# E-12_USB_PD.net
KiCad netlist of a schematic drawn in Altium Designer
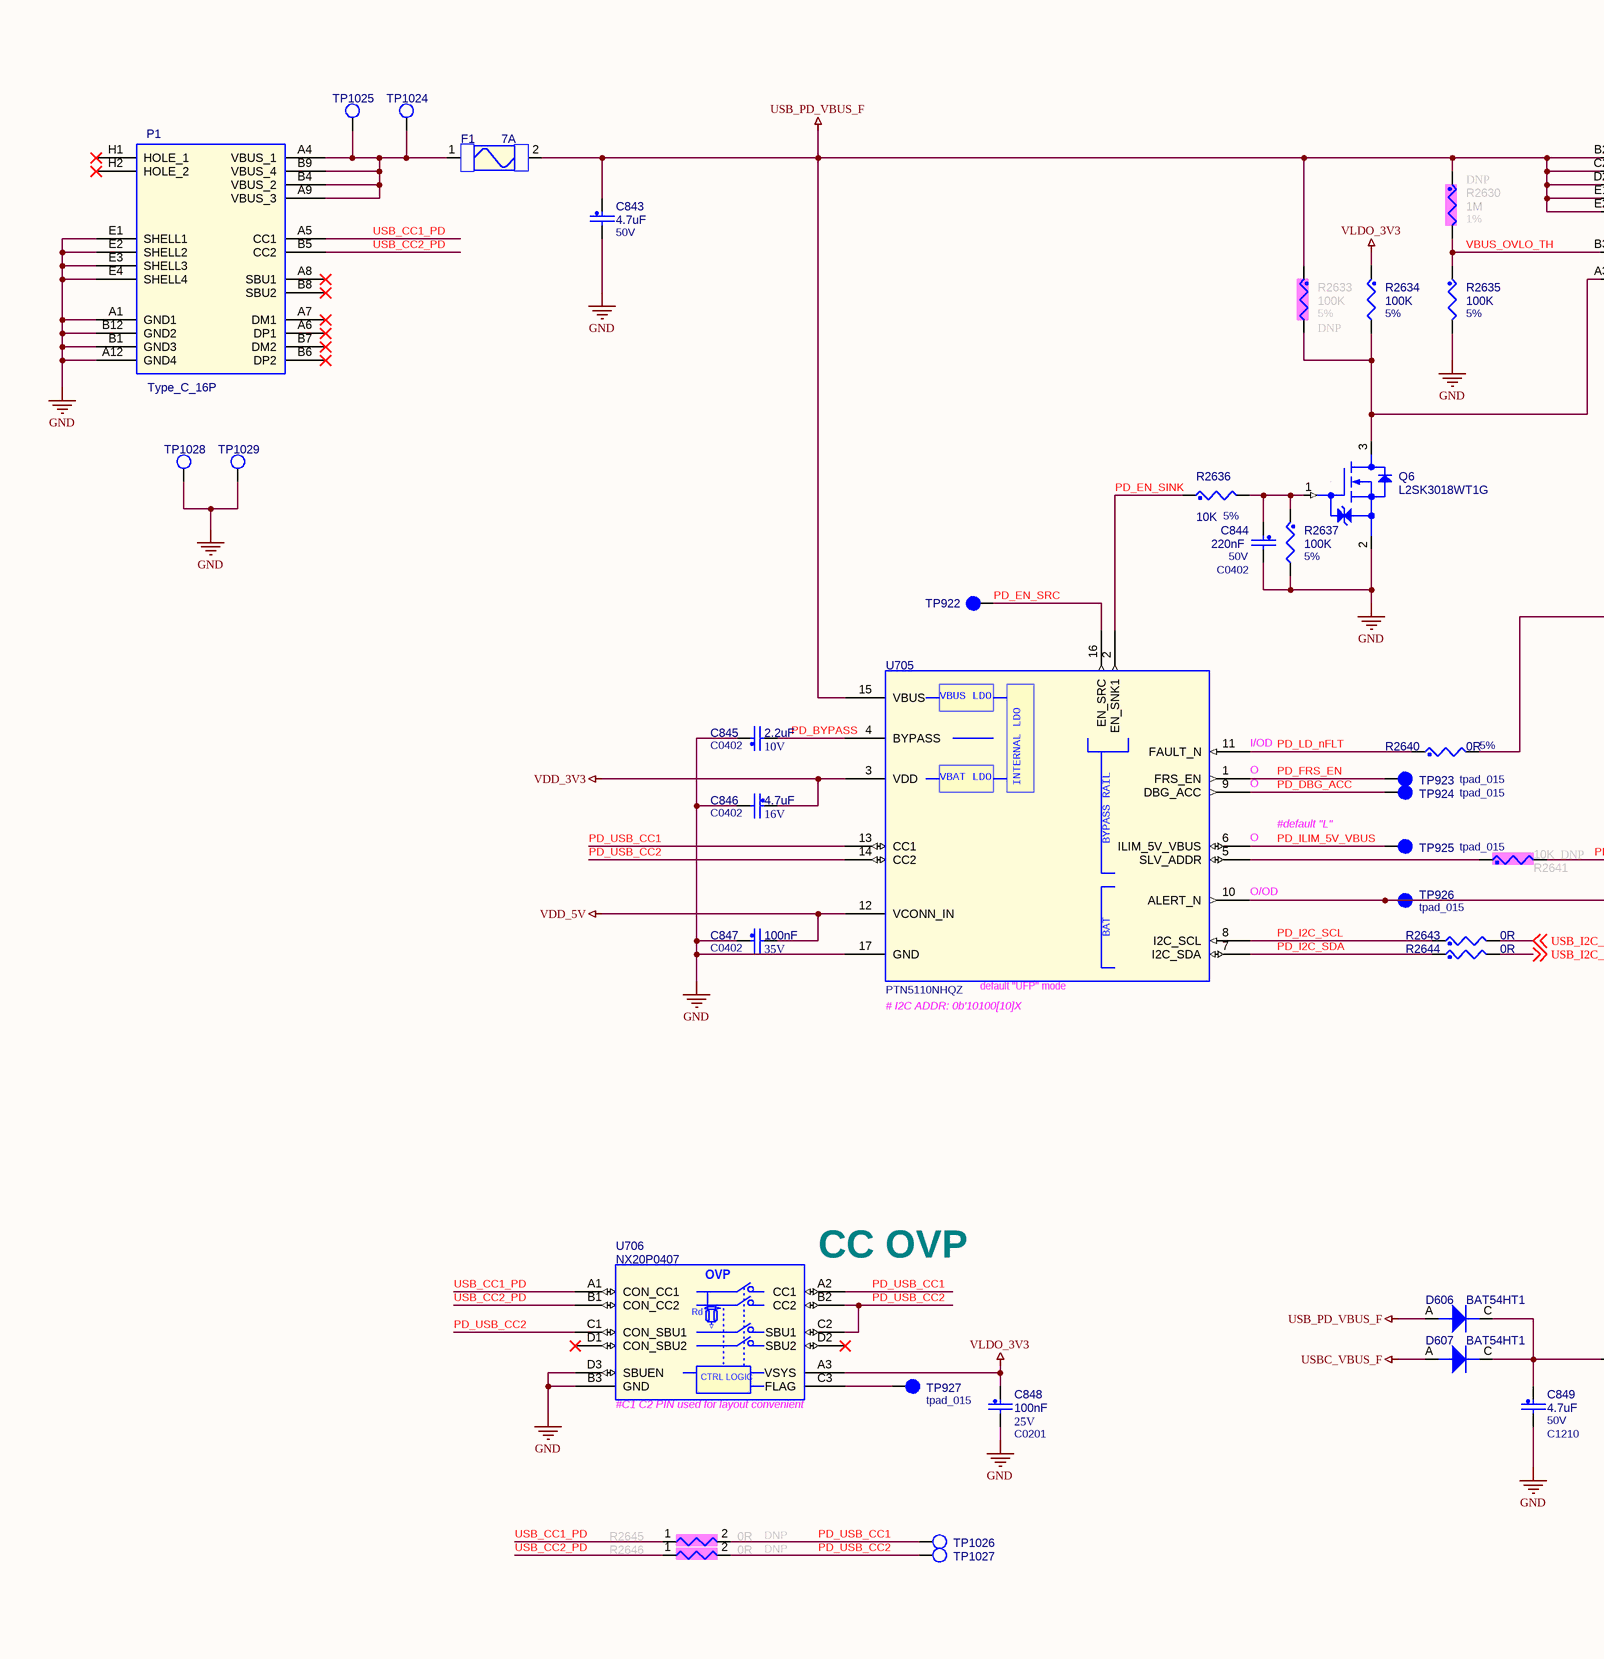
[diagram p0: E-12 USB PD.SchDoc, left]
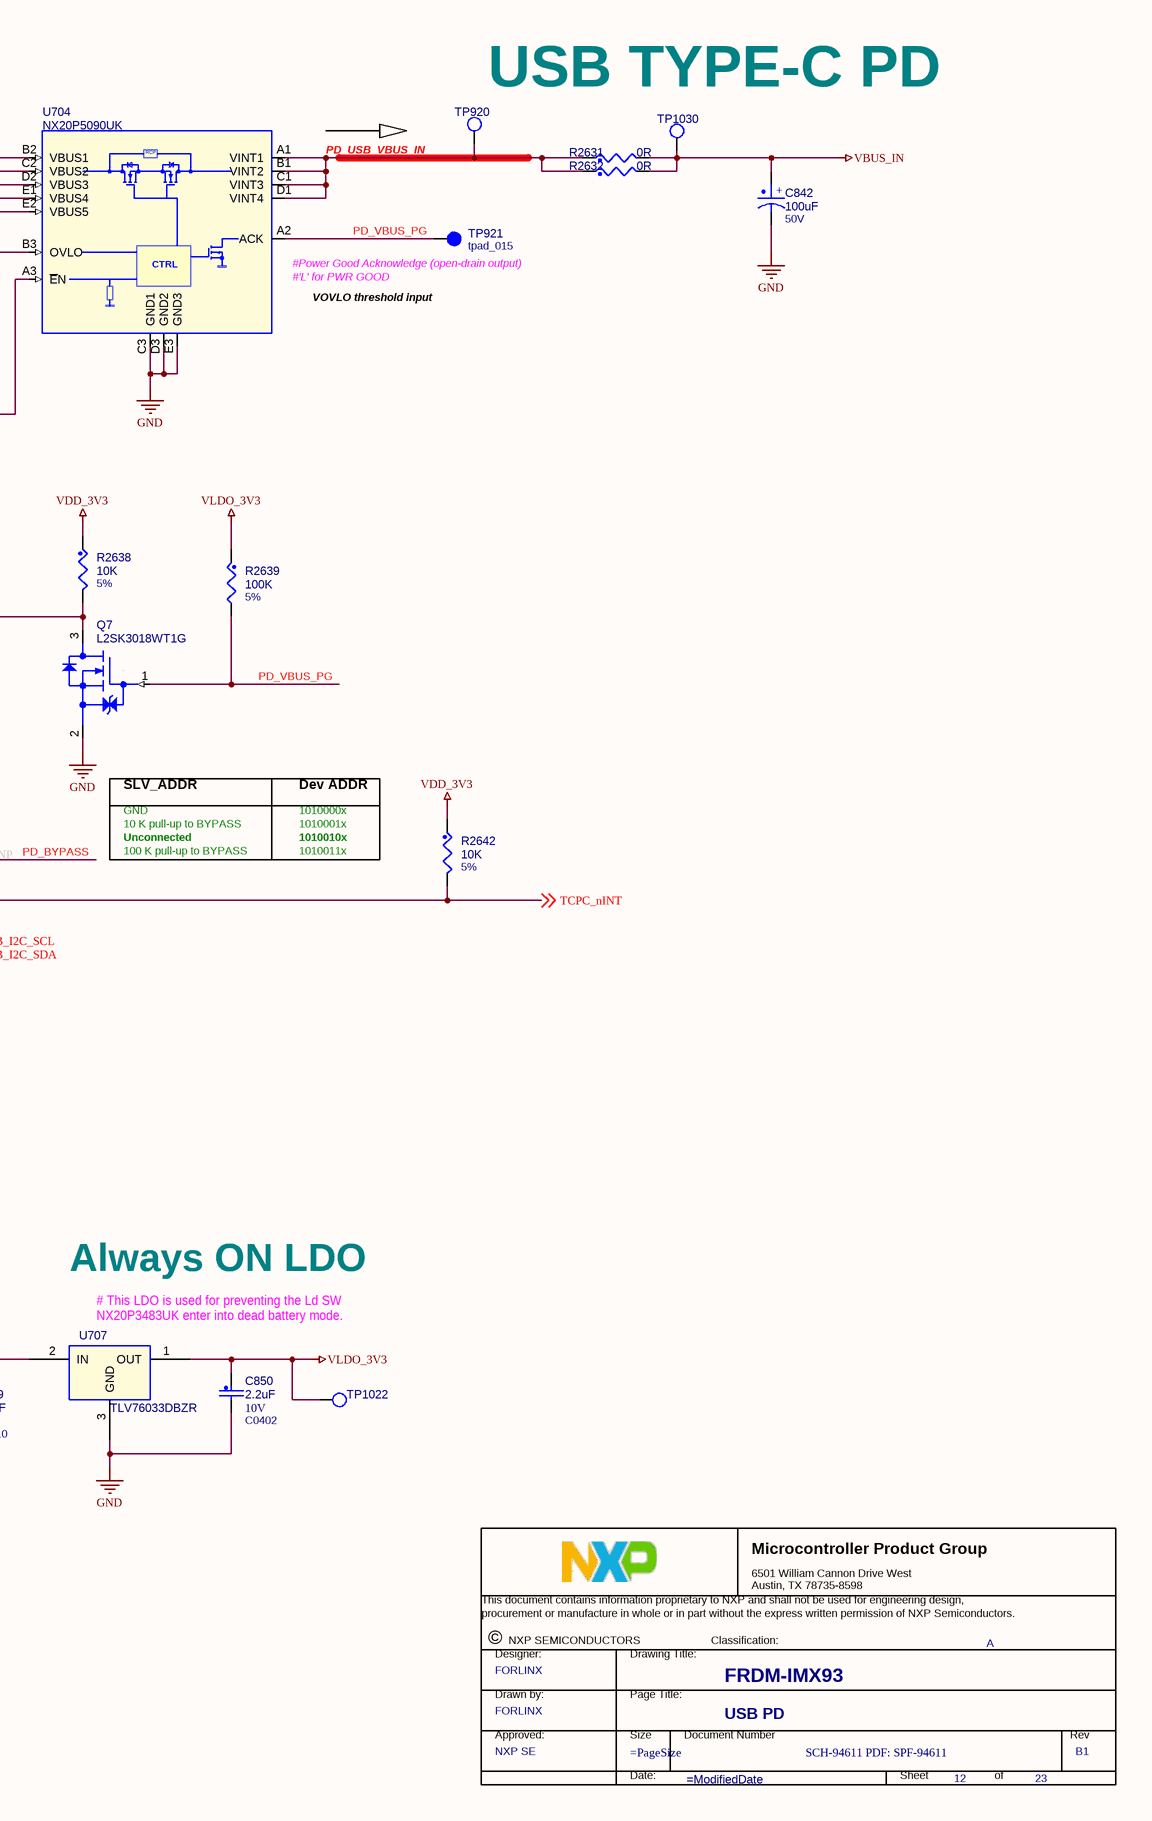
[diagram p1: E-12 USB PD.SchDoc, right]

(export (version "E")
  (design (tool "Eeschema 10.0.6"))
  (components
    (comp (ref "C842")
      (value "100uF")
      (footprint "cce6P3x7p7")
      (description "100uF,35V,6.3*7.7mm")
      (fields (field (name "VOLTAGE") "50V") (field (name "TOLERANCE") "20%"))
      (libsource (lib "*") (part "CAP_POL"))
    )
    (comp (ref "C843")
      (value "4.7uF")
      (footprint "C1210")
      (description "1210,4.7uF,50V,+/-10%,X7R")
      (fields (field (name "VOLTAGE") "50V") (field (name "TOLERANCE") "10%"))
      (libsource (lib "*") (part "CAP_NP"))
    )
    (comp (ref "C844")
      (value "220nF")
      (footprint "C0402")
      (description "0402,220nF,25V,+/-10%,X5R")
      (fields
        (field (name "VOLTAGE") "50V")
        (field (name "TOLERANCE") "10%")
        (field (name "PCB FOOTPRINT") "C0402")
      )
      (libsource (lib "*") (part "CAP_NP"))
    )
    (comp (ref "C845")
      (value "2.2uF")
      (footprint "C0402")
      (description "0402,2.2uF,10V,+/-10%,X5R")
      (fields
        (field (name "VOLTAGE") "10V")
        (field (name "TOLERANCE") "10%")
        (field (name "PCB FOOTPRINT") "C0402")
      )
      (libsource (lib "*") (part "CAP_NP"))
    )
    (comp (ref "C846")
      (value "4.7uF")
      (footprint "C0402")
      (description "0402,4.7uF,10V,+/-10%,X5R")
      (fields (field (name "VOLTAGE") "16V") (field (name "PCB FOOTPRINT") "C0402"))
      (libsource (lib "*") (part "CAP_NP"))
    )
    (comp (ref "C847")
      (value "100nF")
      (footprint "C0402")
      (description "0402,100nF,50V,+/-10%,X5R")
      (fields
        (field (name "VOLTAGE") "35V")
        (field (name "TOLERANCE") "10%")
        (field (name "PCB FOOTPRINT") "C0402")
      )
      (libsource (lib "*") (part "CAP_NP"))
    )
    (comp (ref "C848")
      (value "100nF")
      (footprint "C0201")
      (description "0201,100nF,25V,+/-10%,X5R")
      (fields
        (field (name "TOLERANCE") "10%")
        (field (name "VOLTAGE") "25V")
        (field (name "PCB FOOTPRINT") "C0201")
      )
      (libsource (lib "*") (part "CAP_NP"))
    )
    (comp (ref "C849")
      (value "4.7uF")
      (footprint "C1210")
      (description "1210,4.7uF,50V,+/-10%,X7R")
      (fields
        (field (name "VOLTAGE") "50V")
        (field (name "TOLERANCE") "10%")
        (field (name "PCB FOOTPRINT") "C1210")
      )
      (libsource (lib "*") (part "CAP_NP"))
    )
    (comp (ref "C850")
      (value "2.2uF")
      (footprint "C0402")
      (description "0402,2.2uF,10V,+/-10%,X5R")
      (fields
        (field (name "TOLERANCE") "10%")
        (field (name "VOLTAGE") "10V")
        (field (name "PCB FOOTPRINT") "C0402")
      )
      (libsource (lib "*") (part "CAP_NP"))
    )
    (comp (ref "D606")
      (value "BAT54HT1")
      (footprint "SOD323")
      (description "BAT54HT1G,SOD323")
      (libsource (lib "*") (part "DIODE"))
    )
    (comp (ref "D607")
      (value "BAT54HT1")
      (footprint "SOD323")
      (description "BAT54HT1G,SOD323")
      (libsource (lib "*") (part "DIODE"))
    )
    (comp (ref "F1")
      (value "7A")
      (footprint "fuse_3p4x1p8")
      (description "Fuse,1206,7A,32V")
      (libsource (lib "*") (part "FUSE"))
    )
    (comp (ref "P1")
      (value "Type_C_16P")
      (footprint "TypeC_16P_S")
      (description "USB616FC-C2014216,USB2.0,type-c")
      (libsource (lib "*") (part "Type_C_16P"))
    )
    (comp (ref "Q6")
      (value "L2SK3018WT1G")
      (footprint "sc70_3")
      (libsource (lib "*") (part "NX3008NBKW_SOT323"))
    )
    (comp (ref "Q7")
      (value "L2SK3018WT1G")
      (footprint "sc70_3")
      (libsource (lib "*") (part "NX3008NBKW_SOT323"))
    )
    (comp (ref "R2630")
      (value "1M")
      (footprint "R0201")
      (description "0201,1M,+/-1%")
      (fields (field (name "ASSY_OPT") "DNP") (field (name "TOLERANCE") "1%"))
      (libsource (lib "*") (part "RES"))
    )
    (comp (ref "R2631")
      (value "0R")
      (footprint "R0805")
      (description "0805,0Ohm+/-5%")
      (fields (field (name "VOLTAGE") "150V"))
      (libsource (lib "*") (part "RES"))
    )
    (comp (ref "R2632")
      (value "0R")
      (footprint "R0805")
      (description "0805,0Ohm+/-5%")
      (fields (field (name "VOLTAGE") "150V"))
      (libsource (lib "*") (part "RES"))
    )
    (comp (ref "R2633")
      (value "100K")
      (footprint "R0201")
      (description "0201,100K,+/-1%")
      (fields (field (name "ASSY_OPT") "DNP") (field (name "VOLTAGE") "50V") (field (name "TOLERANCE") "5%"))
      (libsource (lib "*") (part "RES"))
    )
    (comp (ref "R2634")
      (value "100K")
      (footprint "R0201")
      (description "0201,100K,+/-1%")
      (fields (field (name "VOLTAGE") "50V") (field (name "TOLERANCE") "5%"))
      (libsource (lib "*") (part "RES"))
    )
    (comp (ref "R2635")
      (value "100K")
      (footprint "R0201")
      (description "0201,100K,+/-1%")
      (fields (field (name "VOLTAGE") "50V") (field (name "TOLERANCE") "5%"))
      (libsource (lib "*") (part "RES"))
    )
    (comp (ref "R2636")
      (value "10K")
      (footprint "R0201")
      (description "0201,10K,+/-5%")
      (fields (field (name "TOLERANCE") "5%"))
      (libsource (lib "*") (part "RES"))
    )
    (comp (ref "R2637")
      (value "100K")
      (footprint "R0201")
      (description "0201,100K,+/-1%")
      (fields (field (name "TOLERANCE") "5%") (field (name "VOLTAGE") "50V"))
      (libsource (lib "*") (part "RES"))
    )
    (comp (ref "R2638")
      (value "10K")
      (footprint "R0201")
      (description "0201,10K,+/-5%")
      (fields (field (name "TOLERANCE") "5%"))
      (libsource (lib "*") (part "RES"))
    )
    (comp (ref "R2639")
      (value "100K")
      (footprint "R0201")
      (description "0201,100K,+/-1%")
      (fields (field (name "TOLERANCE") "5%") (field (name "VOLTAGE") "50V"))
      (libsource (lib "*") (part "RES"))
    )
    (comp (ref "R2640")
      (value "0R")
      (footprint "R0201")
      (description "0201,0Ohm,+/-5%")
      (fields (field (name "VOLTAGE") "1/16W") (field (name "TOLERANCE") "5%"))
      (libsource (lib "*") (part "RES"))
    )
    (comp (ref "R2641")
      (value "10K")
      (footprint "R0402")
      (description "0402,10K,+/-1%")
      (fields (field (name "ASSY_OPT") "DNP") (field (name "TOLERANCE") "5%"))
      (libsource (lib "*") (part "RES"))
    )
    (comp (ref "R2642")
      (value "10K")
      (footprint "R0201")
      (description "0201,10K,+/-5%")
      (fields (field (name "TOLERANCE") "5%"))
      (libsource (lib "*") (part "RES"))
    )
    (comp (ref "R2643")
      (value "0R")
      (footprint "R0201")
      (description "0201,0Ohm,+/-5%")
      (fields (field (name "TOLERANCE") "5%") (field (name "VOLTAGE") "1/16W"))
      (libsource (lib "*") (part "RES"))
    )
    (comp (ref "R2644")
      (value "0R")
      (footprint "R0201")
      (description "0201,0Ohm,+/-5%")
      (fields (field (name "TOLERANCE") "5%") (field (name "VOLTAGE") "1/16W"))
      (libsource (lib "*") (part "RES"))
    )
    (comp (ref "R2645")
      (value "0R")
      (footprint "R0201")
      (description "0201,0Ohm,+/-5%")
      (fields
        (field (name "TOLERANCE") "1%")
        (field (name "MANUFACTURER") "YAGEO")
        (field (name "ASSY_OPT") "DNP")
        (field (name "CREATED BY") "YTL")
      )
      (libsource (lib "*") (part "RESISTOR"))
    )
    (comp (ref "R2646")
      (value "0R")
      (footprint "R0201")
      (description "0201,0Ohm,+/-5%")
      (fields
        (field (name "TOLERANCE") "1%")
        (field (name "ASSY_OPT") "DNP")
        (field (name "MANUFACTURER") "YAGEO")
        (field (name "CREATED BY") "YTL")
      )
      (libsource (lib "*") (part "RESISTOR"))
    )
    (comp (ref "TP920")
      (value "TPAD_020")
      (footprint "tpad_020")
      (description "no part to order")
      (libsource (lib "*") (part "T POINT R"))
    )
    (comp (ref "TP921")
      (value "TPAD_015")
      (footprint "tpad_015")
      (description "no part to order")
      (fields (field (name "PCB FOOTPRINT") "tpad_015"))
      (libsource (lib "*") (part "TESTLOOP"))
    )
    (comp (ref "TP922")
      (value "TPAD_015")
      (footprint "tpad_015")
      (description "no part to order")
      (libsource (lib "*") (part "TESTLOOP"))
    )
    (comp (ref "TP923")
      (value "TPAD_015")
      (footprint "tpad_015")
      (description "no part to order")
      (fields (field (name "PCB FOOTPRINT") "tpad_015"))
      (libsource (lib "*") (part "TESTLOOP"))
    )
    (comp (ref "TP924")
      (value "TPAD_015")
      (footprint "tpad_015")
      (description "no part to order")
      (fields (field (name "PCB FOOTPRINT") "tpad_015"))
      (libsource (lib "*") (part "TESTLOOP"))
    )
    (comp (ref "TP925")
      (value "TPAD_015")
      (footprint "tpad_015")
      (description "no part to order")
      (fields (field (name "PCB FOOTPRINT") "tpad_015"))
      (libsource (lib "*") (part "TESTLOOP"))
    )
    (comp (ref "TP926")
      (value "TPAD_015")
      (footprint "tpad_015")
      (description "no part to order")
      (fields (field (name "PCB FOOTPRINT") "tpad_015"))
      (libsource (lib "*") (part "TESTLOOP"))
    )
    (comp (ref "TP927")
      (value "TPAD_015")
      (footprint "tpad_015")
      (description "no part to order")
      (fields (field (name "PCB FOOTPRINT") "tpad_015"))
      (libsource (lib "*") (part "TESTLOOP"))
    )
    (comp (ref "TP1022")
      (value "TPAD_020")
      (footprint "tpad_020")
      (description "no part to order")
      (libsource (lib "*") (part "T POINT R"))
    )
    (comp (ref "TP1024")
      (value "TPAD_020")
      (footprint "tpad_020")
      (description "no part to order")
      (libsource (lib "*") (part "T POINT R"))
    )
    (comp (ref "TP1025")
      (value "TPAD_020")
      (footprint "tpad_020")
      (description "no part to order")
      (libsource (lib "*") (part "T POINT R"))
    )
    (comp (ref "TP1026")
      (value "TPAD_020")
      (footprint "tpad_020")
      (description "no part to order")
      (libsource (lib "*") (part "T POINT R"))
    )
    (comp (ref "TP1027")
      (value "TPAD_020")
      (footprint "tpad_020")
      (description "no part to order")
      (libsource (lib "*") (part "T POINT R"))
    )
    (comp (ref "TP1028")
      (value "TPAD_020")
      (footprint "tpad_020")
      (description "no part to order")
      (libsource (lib "*") (part "T POINT R"))
    )
    (comp (ref "TP1029")
      (value "TPAD_020")
      (footprint "tpad_020")
      (description "no part to order")
      (libsource (lib "*") (part "T POINT R"))
    )
    (comp (ref "TP1030")
      (value "TPAD_020")
      (footprint "tpad_020")
      (description "no part to order")
      (libsource (lib "*") (part "T POINT R"))
    )
    (comp (ref "U704")
      (value "NX20P5090UK")
      (footprint "wlcsp15_0p5_1p57x2p59")
      (description "IC USB PWR SW 5A 2.5-20V WLCSP15")
      (fields (field (name "MANUFACTURER") "NXP Semiconductors"))
      (libsource (lib "*") (part "NX20P5090UK_15P_A"))
    )
    (comp (ref "U705")
      (value "PTN5110")
      (footprint "hx2qfn16_0p4_2p7x2p7")
      (description "IC USB PD PHY 1PORT 2.7-5.5V HX2QFN16")
      (fields (field (name "VOLTAGE") "2.7-5.5V") (field (name "MFG_PN01") "PTN5110NHQZ"))
      (libsource (lib "*") (part "PTN5110_QFN16"))
    )
    (comp (ref "U706")
      (value "NX20P0407")
      (footprint "wlcsp12_0p4_1p3x1p7mm_smdp")
      (description "IC USB TYPE C PROTECTION +15KV/+8KV ESD WLCSP12")
      (fields
        (field (name "MANUFACTURER") "NXP Semiconductors")
        (field (name "MANUFACTURER PART NUMBER") "NX20P5090UK")
      )
      (libsource (lib "*") (part "NX20P0407_WLCSP12_A"))
    )
    (comp (ref "U707")
      (value "TLV76033DBZR")
      (footprint "sot23_a")
      (libsource (lib "*") (part "SGM2034-3_0.3YN3G"))
    )
  )
  (nets
    (net (code "1") (name "/PD_BYPASS") (class "Default")
      (node (ref "C845") (pin "2") (pinfunction "2_2") (pintype "passive"))
      (node (ref "R2641") (pin "2") (pinfunction "2_2") (pintype "passive"))
      (node (ref "U705") (pin "4") (pinfunction "BYPASS_4") (pintype "passive"))
    )
    (net (code "2") (name "/PD_DBG_ACC") (class "Default")
      (node (ref "TP924") (pin "1") (pinfunction "Pin1_1") (pintype "passive"))
      (node (ref "U705") (pin "9") (pinfunction "DBG_ACC_9") (pintype "output"))
    )
    (net (code "3") (name "/PD_EN_SINK") (class "Default")
      (node (ref "R2636") (pin "1") (pinfunction "1_1") (pintype "passive"))
      (node (ref "U705") (pin "2") (pinfunction "EN_SNK1_2") (pintype "output"))
    )
    (net (code "4") (name "/PD_EN_SRC") (class "Default")
      (node (ref "TP922") (pin "1") (pinfunction "Pin1_1") (pintype "passive"))
      (node (ref "U705") (pin "16") (pinfunction "EN_SRC_16") (pintype "output"))
    )
    (net (code "5") (name "/PD_FRS_EN") (class "Default")
      (node (ref "TP923") (pin "1") (pinfunction "Pin1_1") (pintype "passive"))
      (node (ref "U705") (pin "1") (pinfunction "FRS_EN_1") (pintype "output"))
    )
    (net (code "6") (name "/PD_I2C_SCL") (class "Default")
      (node (ref "R2643") (pin "1") (pinfunction "1_1") (pintype "passive"))
      (node (ref "U705") (pin "8") (pinfunction "I2C_SCL_8") (pintype "input"))
    )
    (net (code "7") (name "/PD_I2C_SDA") (class "Default")
      (node (ref "R2644") (pin "1") (pinfunction "1_1") (pintype "passive"))
      (node (ref "U705") (pin "7") (pinfunction "I2C_SDA_7") (pintype "bidirectional"))
    )
    (net (code "8") (name "/PD_ILIM_5V_VBUS") (class "Default")
      (node (ref "TP925") (pin "1") (pinfunction "Pin1_1") (pintype "passive"))
      (node (ref "U705") (pin "6") (pinfunction "ILIM_5V_VBUS_6") (pintype "bidirectional"))
    )
    (net (code "9") (name "/PD_LD_nFLT") (class "Default")
      (node (ref "R2640") (pin "1") (pinfunction "1_1") (pintype "passive"))
      (node (ref "U705") (pin "11") (pinfunction "FAULT_N_11") (pintype "input"))
    )
    (net (code "10") (name "/PD_USB_CC1") (class "Default")
      (node (ref "R2645") (pin "2") (pinfunction "2_2") (pintype "passive"))
      (node (ref "TP1026") (pin "1") (pinfunction "TP_1") (pintype "passive"))
      (node (ref "U705") (pin "13") (pinfunction "CC1_13") (pintype "bidirectional"))
      (node (ref "U706") (pin "A2") (pinfunction "CC1_A2") (pintype "bidirectional"))
    )
    (net (code "11") (name "/PD_USB_CC2") (class "Default")
      (node (ref "R2646") (pin "2") (pinfunction "2_2") (pintype "passive"))
      (node (ref "TP1027") (pin "1") (pinfunction "TP_1") (pintype "passive"))
      (node (ref "U705") (pin "14") (pinfunction "CC2_14") (pintype "bidirectional"))
      (node (ref "U706") (pin "B2") (pinfunction "CC2_B2") (pintype "bidirectional"))
      (node (ref "U706") (pin "C1") (pinfunction "CON_SBU1_C1") (pintype "bidirectional"))
      (node (ref "U706") (pin "C2") (pinfunction "SBU1_C2") (pintype "bidirectional"))
    )
    (net (code "12") (name "/PD_USB_VBUS_IN") (class "Default")
      (node (ref "R2631") (pin "1") (pinfunction "1_1") (pintype "passive"))
      (node (ref "R2632") (pin "1") (pinfunction "1_1") (pintype "passive"))
      (node (ref "TP920") (pin "1") (pinfunction "TP_1") (pintype "passive"))
      (node (ref "U704") (pin "A1") (pinfunction "VINT1_A1") (pintype "power_in"))
      (node (ref "U704") (pin "B1") (pinfunction "VINT2_B1") (pintype "power_in"))
      (node (ref "U704") (pin "C1") (pinfunction "VINT3_C1") (pintype "power_in"))
      (node (ref "U704") (pin "D1") (pinfunction "VINT4_D1") (pintype "power_in"))
    )
    (net (code "13") (name "/PD_VBUS_PG") (class "Default")
      (node (ref "Q7") (pin "1") (pinfunction "GATE_1") (pintype "input"))
      (node (ref "R2639") (pin "2") (pinfunction "2_2") (pintype "passive"))
      (node (ref "TP921") (pin "1") (pinfunction "Pin1_1") (pintype "passive"))
      (node (ref "U704") (pin "A2") (pinfunction "ACK_A2") (pintype "open_collector"))
    )
    (net (code "14") (name "/USB_CC1_PD") (class "Default")
      (node (ref "P1") (pin "A5") (pinfunction "CC1_A5") (pintype "passive"))
      (node (ref "R2645") (pin "1") (pinfunction "1_1") (pintype "passive"))
      (node (ref "U706") (pin "A1") (pinfunction "CON_CC1_A1") (pintype "bidirectional"))
    )
    (net (code "15") (name "/USB_CC2_PD") (class "Default")
      (node (ref "P1") (pin "B5") (pinfunction "CC2_B5") (pintype "passive"))
      (node (ref "R2646") (pin "1") (pinfunction "1_1") (pintype "passive"))
      (node (ref "U706") (pin "B1") (pinfunction "CON_CC2_B1") (pintype "bidirectional"))
    )
    (net (code "16") (name "/VBUS_OVLO_TH") (class "Default")
      (node (ref "R2630") (pin "2") (pinfunction "2_2") (pintype "passive"))
      (node (ref "R2635") (pin "1") (pinfunction "1_1") (pintype "passive"))
      (node (ref "U704") (pin "B3") (pinfunction "OVLO_B3") (pintype "input"))
    )
    (net (code "17") (name "GND") (class "Default")
      (node (ref "C842") (pin "2") (pinfunction "2_2") (pintype "passive"))
      (node (ref "C843") (pin "2") (pinfunction "2_2") (pintype "passive"))
      (node (ref "C844") (pin "2") (pinfunction "2_2") (pintype "passive"))
      (node (ref "C845") (pin "1") (pinfunction "1_1") (pintype "passive"))
      (node (ref "C846") (pin "2") (pinfunction "2_2") (pintype "passive"))
      (node (ref "C847") (pin "1") (pinfunction "1_1") (pintype "passive"))
      (node (ref "C848") (pin "2") (pinfunction "2_2") (pintype "passive"))
      (node (ref "C849") (pin "2") (pinfunction "2_2") (pintype "passive"))
      (node (ref "C850") (pin "2") (pinfunction "2_2") (pintype "passive"))
      (node (ref "P1") (pin "A1") (pinfunction "GND1_A1") (pintype "passive"))
      (node (ref "P1") (pin "A12") (pinfunction "GND4_A12") (pintype "passive"))
      (node (ref "P1") (pin "B1") (pinfunction "GND3_B1") (pintype "passive"))
      (node (ref "P1") (pin "B12") (pinfunction "GND2_B12") (pintype "passive"))
      (node (ref "P1") (pin "E1") (pinfunction "SHELL1_E1") (pintype "passive"))
      (node (ref "P1") (pin "E2") (pinfunction "SHELL2_E2") (pintype "passive"))
      (node (ref "P1") (pin "E3") (pinfunction "SHELL3_E3") (pintype "passive"))
      (node (ref "P1") (pin "E4") (pinfunction "SHELL4_E4") (pintype "passive"))
      (node (ref "Q6") (pin "2") (pinfunction "SOURCE_2") (pintype "passive"))
      (node (ref "Q7") (pin "2") (pinfunction "SOURCE_2") (pintype "passive"))
      (node (ref "R2635") (pin "2") (pinfunction "2_2") (pintype "passive"))
      (node (ref "R2637") (pin "2") (pinfunction "2_2") (pintype "passive"))
      (node (ref "TP1028") (pin "1") (pinfunction "TP_1") (pintype "passive"))
      (node (ref "TP1029") (pin "1") (pinfunction "TP_1") (pintype "passive"))
      (node (ref "U704") (pin "C3") (pinfunction "GND1_C3") (pintype "power_in"))
      (node (ref "U704") (pin "D3") (pinfunction "GND2_D3") (pintype "power_in"))
      (node (ref "U704") (pin "E3") (pinfunction "GND3_E3") (pintype "power_in"))
      (node (ref "U705") (pin "17") (pinfunction "GND_17") (pintype "power_in"))
      (node (ref "U706") (pin "B3") (pinfunction "GND_B3") (pintype "power_in"))
      (node (ref "U706") (pin "D3") (pinfunction "SBUEN_D3") (pintype "bidirectional"))
      (node (ref "U707") (pin "3") (pinfunction "GND_3") (pintype "passive"))
    )
    (net (code "18") (name "Net-(D606-CATHODE)") (class "Default")
      (node (ref "C849") (pin "1") (pinfunction "1_1") (pintype "passive"))
      (node (ref "D606") (pin "C") (pinfunction "CATHODE_C") (pintype "passive"))
      (node (ref "D607") (pin "C") (pinfunction "CATHODE_C") (pintype "passive"))
      (node (ref "U707") (pin "2") (pinfunction "IN_2") (pintype "passive"))
    )
    (net (code "19") (name "Net-(P1-VBUS_1)") (class "Default")
      (node (ref "F1") (pin "1") (pinfunction "1_1") (pintype "passive"))
      (node (ref "P1") (pin "A4") (pinfunction "VBUS_1_A4") (pintype "passive"))
      (node (ref "P1") (pin "A9") (pinfunction "VBUS_3_A9") (pintype "passive"))
      (node (ref "P1") (pin "B4") (pinfunction "VBUS_2_B4") (pintype "passive"))
      (node (ref "P1") (pin "B9") (pinfunction "VBUS_4_B9") (pintype "passive"))
      (node (ref "TP1024") (pin "1") (pinfunction "TP_1") (pintype "passive"))
      (node (ref "TP1025") (pin "1") (pinfunction "TP_1") (pintype "passive"))
    )
    (net (code "20") (name "Net-(Q6-DRAIN)") (class "Default")
      (node (ref "Q6") (pin "3") (pinfunction "DRAIN_3") (pintype "passive"))
      (node (ref "R2633") (pin "2") (pinfunction "2_2") (pintype "passive"))
      (node (ref "R2634") (pin "2") (pinfunction "2_2") (pintype "passive"))
      (node (ref "U704") (pin "A3") (pinfunction "~{E}N_A3") (pintype "input"))
    )
    (net (code "21") (name "Net-(Q6-GATE)") (class "Default")
      (node (ref "C844") (pin "1") (pinfunction "1_1") (pintype "passive"))
      (node (ref "Q6") (pin "1") (pinfunction "GATE_1") (pintype "input"))
      (node (ref "R2636") (pin "2") (pinfunction "2_2") (pintype "passive"))
      (node (ref "R2637") (pin "1") (pinfunction "1_1") (pintype "passive"))
    )
    (net (code "22") (name "Net-(Q7-DRAIN)") (class "Default")
      (node (ref "Q7") (pin "3") (pinfunction "DRAIN_3") (pintype "passive"))
      (node (ref "R2638") (pin "2") (pinfunction "2_2") (pintype "passive"))
      (node (ref "R2640") (pin "2") (pinfunction "2_2") (pintype "passive"))
    )
    (net (code "23") (name "Net-(TP927-Pin1)") (class "Default")
      (node (ref "TP927") (pin "1") (pinfunction "Pin1_1") (pintype "passive"))
      (node (ref "U706") (pin "C3") (pinfunction "FLAG_C3") (pintype "open_collector"))
    )
    (net (code "24") (name "Net-(U705-SLV_ADDR)") (class "Default")
      (node (ref "R2641") (pin "1") (pinfunction "1_1") (pintype "passive"))
      (node (ref "U705") (pin "5") (pinfunction "SLV_ADDR_5") (pintype "bidirectional"))
    )
    (net (code "25") (name "TCPC_nINT") (class "Default")
      (node (ref "R2642") (pin "2") (pinfunction "2_2") (pintype "passive"))
      (node (ref "TP926") (pin "1") (pinfunction "Pin1_1") (pintype "passive"))
      (node (ref "U705") (pin "10") (pinfunction "ALERT_N_10") (pintype "output"))
    )
    (net (code "26") (name "USBC_VBUS_F") (class "Default")
      (node (ref "D607") (pin "A") (pinfunction "ANODE_A") (pintype "passive"))
    )
    (net (code "27") (name "USB_I2C_SCL") (class "Default")
      (node (ref "R2643") (pin "2") (pinfunction "2_2") (pintype "passive"))
    )
    (net (code "28") (name "USB_I2C_SDA") (class "Default")
      (node (ref "R2644") (pin "2") (pinfunction "2_2") (pintype "passive"))
    )
    (net (code "29") (name "USB_PD_VBUS_F") (class "Default")
      (node (ref "C843") (pin "1") (pinfunction "1_1") (pintype "passive"))
      (node (ref "D606") (pin "A") (pinfunction "ANODE_A") (pintype "passive"))
      (node (ref "F1") (pin "2") (pinfunction "2_2") (pintype "passive"))
      (node (ref "R2630") (pin "1") (pinfunction "1_1") (pintype "passive"))
      (node (ref "R2633") (pin "1") (pinfunction "1_1") (pintype "passive"))
      (node (ref "U704") (pin "B2") (pinfunction "VBUS1_B2") (pintype "input"))
      (node (ref "U704") (pin "C2") (pinfunction "VBUS2_C2") (pintype "input"))
      (node (ref "U704") (pin "D2") (pinfunction "VBUS3_D2") (pintype "input"))
      (node (ref "U704") (pin "E1") (pinfunction "VBUS4_E1") (pintype "input"))
      (node (ref "U704") (pin "E2") (pinfunction "VBUS5_E2") (pintype "input"))
      (node (ref "U705") (pin "15") (pinfunction "VBUS_15") (pintype "power_in"))
    )
    (net (code "30") (name "VBUS_IN") (class "Default")
      (node (ref "C842") (pin "1") (pinfunction "1_1") (pintype "passive"))
      (node (ref "R2631") (pin "2") (pinfunction "2_2") (pintype "passive"))
      (node (ref "R2632") (pin "2") (pinfunction "2_2") (pintype "passive"))
      (node (ref "TP1030") (pin "1") (pinfunction "TP_1") (pintype "passive"))
    )
    (net (code "31") (name "VDD_3V3") (class "Default")
      (node (ref "C846") (pin "1") (pinfunction "1_1") (pintype "passive"))
      (node (ref "R2638") (pin "1") (pinfunction "1_1") (pintype "passive"))
      (node (ref "R2642") (pin "1") (pinfunction "1_1") (pintype "passive"))
      (node (ref "U705") (pin "3") (pinfunction "VDD_3") (pintype "power_in"))
    )
    (net (code "32") (name "VDD_5V") (class "Default")
      (node (ref "C847") (pin "2") (pinfunction "2_2") (pintype "passive"))
      (node (ref "U705") (pin "12") (pinfunction "VCONN_IN_12") (pintype "power_in"))
    )
    (net (code "33") (name "VLDO_3V3") (class "Default")
      (node (ref "C848") (pin "1") (pinfunction "1_1") (pintype "passive"))
      (node (ref "C850") (pin "1") (pinfunction "1_1") (pintype "passive"))
      (node (ref "R2634") (pin "1") (pinfunction "1_1") (pintype "passive"))
      (node (ref "R2639") (pin "1") (pinfunction "1_1") (pintype "passive"))
      (node (ref "TP1022") (pin "1") (pinfunction "TP_1") (pintype "passive"))
      (node (ref "U706") (pin "A3") (pinfunction "VSYS_A3") (pintype "power_in"))
      (node (ref "U707") (pin "1") (pinfunction "OUT_1") (pintype "passive"))
    )
    (net (code "34") (name "unconnected-(P1-DM1-PadA7)") (class "Default")
      (node (ref "P1") (pin "A7") (pinfunction "DM1_A7") (pintype "passive+no_connect"))
    )
    (net (code "35") (name "unconnected-(P1-DM2-PadB7)") (class "Default")
      (node (ref "P1") (pin "B7") (pinfunction "DM2_B7") (pintype "passive+no_connect"))
    )
    (net (code "36") (name "unconnected-(P1-DP1-PadA6)") (class "Default")
      (node (ref "P1") (pin "A6") (pinfunction "DP1_A6") (pintype "passive+no_connect"))
    )
    (net (code "37") (name "unconnected-(P1-DP2-PadB6)") (class "Default")
      (node (ref "P1") (pin "B6") (pinfunction "DP2_B6") (pintype "passive+no_connect"))
    )
    (net (code "38") (name "unconnected-(P1-HOLE_1-PadH1)") (class "Default")
      (node (ref "P1") (pin "H1") (pinfunction "HOLE_1_H1") (pintype "passive+no_connect"))
    )
    (net (code "39") (name "unconnected-(P1-HOLE_2-PadH2)") (class "Default")
      (node (ref "P1") (pin "H2") (pinfunction "HOLE_2_H2") (pintype "passive+no_connect"))
    )
    (net (code "40") (name "unconnected-(P1-SBU1-PadA8)") (class "Default")
      (node (ref "P1") (pin "A8") (pinfunction "SBU1_A8") (pintype "passive+no_connect"))
    )
    (net (code "41") (name "unconnected-(P1-SBU2-PadB8)") (class "Default")
      (node (ref "P1") (pin "B8") (pinfunction "SBU2_B8") (pintype "passive+no_connect"))
    )
    (net (code "42") (name "unconnected-(U706-CON_SBU2-PadD1)") (class "Default")
      (node (ref "U706") (pin "D1") (pinfunction "CON_SBU2_D1") (pintype "bidirectional+no_connect"))
    )
    (net (code "43") (name "unconnected-(U706-SBU2-PadD2)") (class "Default")
      (node (ref "U706") (pin "D2") (pinfunction "SBU2_D2") (pintype "bidirectional+no_connect"))
    )
  )
)
